# PWMSoldeerbout.net
KiCad netlist of a schematic drawn in Altium Designer
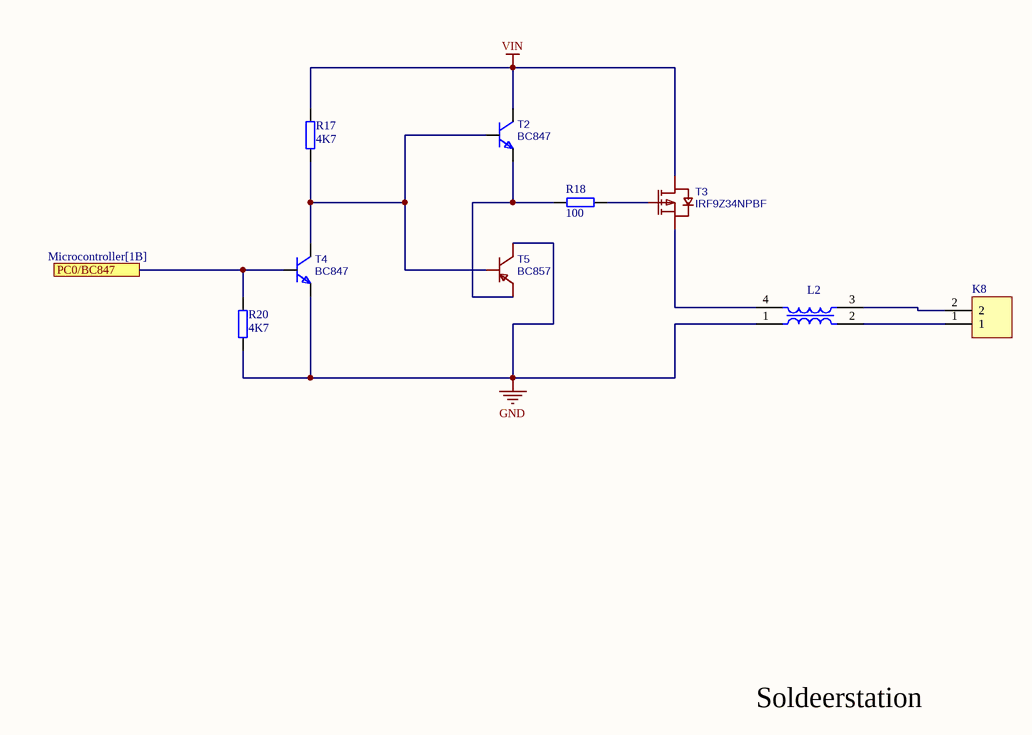
[diagram p0: PWMSoldeerbout.SchDoc]

(export (version "E")
  (design (tool "Eeschema 10.0.6"))
  (components
    (comp (ref "K8")
      (value "~")
      (footprint "Terminal_2")
      (libsource (lib "SoldeerStation") (part "K Terminal_2"))
    )
    (comp (ref "L2")
      (value "~")
      (footprint "L1 Smoorspoel")
      (description "Common Mode Chokes / Filters 170ohms 100MHz 10A 1 Choke SMD")
      (fields
        (field (name "MOUSER PART NUMBER") "875-CM2545X171R-10")
        (field (name "MANUFACTURER_PART_NUMBER") "CM2545X171R-10")
      )
      (libsource (lib "SoldeerStation") (part "L2 Common Mode Choke"))
    )
    (comp (ref "R17")
      (value "4K7")
      (footprint "RESC2013X50X30ML20T20")
      (fields (field (name "MANUFACTURER") "Vishay Dale") (field (name "PART NUMBER") "CRCW08050000Z0EA"))
      (libsource (lib "SoldeerStation") (part "R Resistor"))
    )
    (comp (ref "R18")
      (value "100")
      (footprint "RESC2013X50X30ML20T20")
      (fields (field (name "MANUFACTURER") "Vishay Dale") (field (name "PART NUMBER") "CRCW08050000Z0EA"))
      (libsource (lib "SoldeerStation") (part "R Resistor"))
    )
    (comp (ref "R20")
      (value "4K7")
      (footprint "RESC2013X50X30ML20T20")
      (fields (field (name "MANUFACTURER") "Vishay Dale") (field (name "PART NUMBER") "CRCW08050000Z0EA"))
      (libsource (lib "SoldeerStation") (part "R Resistor"))
    )
    (comp (ref "T2")
      (value "BC847")
      (footprint "T1,2,4 Bipolar Transistors")
      (description "BC847C_C3027113")
      (fields
        (field (name "BOM_SUPPLIER PART") "C3027113")
        (field (name "BOM_MANUFACTURER PART") "BC847C")
        (field (name "CONTRIBUTOR") "lcsc")
      )
      (libsource (lib "SoldeerStation") (part "T1,2,4 transisitors"))
    )
    (comp (ref "T3")
      (value "IRF9Z34NPBF")
      (footprint "T3 MOSFET-P")
      (fields (field (name "BOM_SUPPLIER PART") "C500523") (field (name "CONTRIBUTOR") "LCSC"))
      (libsource (lib "SoldeerStation") (part "T3 MOSFET-P"))
    )
    (comp (ref "T4")
      (value "BC847")
      (footprint "T1,2,4 Bipolar Transistors")
      (description "BC847C_C3027113")
      (fields
        (field (name "BOM_SUPPLIER PART") "C3027113")
        (field (name "BOM_MANUFACTURER PART") "BC847C")
        (field (name "CONTRIBUTOR") "lcsc")
      )
      (libsource (lib "SoldeerStation") (part "T1,2,4 transisitors"))
    )
    (comp (ref "T5")
      (value "BC857")
      (footprint "T5 Bipolar Transistors")
      (description "BC857 3G")
      (fields (field (name "BOM_SUPPLIER PART") "C2139"))
      (libsource (lib "SoldeerStation") (part "T5 Bipolar Transistor"))
    )
  )
  (nets
    (net (code "1") (name "/PC0{slash}BC847") (class "Default")
      (node (ref "R20") (pin "2") (pinfunction "2_2") (pintype "passive"))
      (node (ref "T4") (pin "1") (pinfunction "B_1") (pintype "passive"))
    )
    (net (code "2") (name "GND") (class "Default")
      (node (ref "L2") (pin "1") (pintype "passive"))
      (node (ref "R20") (pin "1") (pinfunction "1_1") (pintype "passive"))
      (node (ref "T4") (pin "2") (pinfunction "E_2") (pintype "passive"))
      (node (ref "T5") (pin "3") (pinfunction "3_3") (pintype "passive"))
    )
    (net (code "3") (name "Net-(K8-Pad1)") (class "Default")
      (node (ref "K8") (pin "1") (pinfunction "1_1") (pintype "passive"))
      (node (ref "L2") (pin "2") (pintype "passive"))
    )
    (net (code "4") (name "Net-(K8-Pad2)") (class "Default")
      (node (ref "K8") (pin "2") (pinfunction "2_2") (pintype "passive"))
      (node (ref "L2") (pin "3") (pintype "passive"))
    )
    (net (code "5") (name "Net-(T2-B)") (class "Default")
      (node (ref "R17") (pin "1") (pinfunction "1_1") (pintype "passive"))
      (node (ref "T2") (pin "1") (pinfunction "B_1") (pintype "passive"))
      (node (ref "T4") (pin "3") (pinfunction "C_3") (pintype "passive"))
      (node (ref "T5") (pin "1") (pinfunction "1_1") (pintype "passive"))
    )
    (net (code "6") (name "Net-(T2-E)") (class "Default")
      (node (ref "R18") (pin "2") (pinfunction "2_2") (pintype "passive"))
      (node (ref "T2") (pin "2") (pinfunction "E_2") (pintype "passive"))
      (node (ref "T5") (pin "2") (pinfunction "2_2") (pintype "passive"))
    )
    (net (code "7") (name "Net-(T3-G)") (class "Default")
      (node (ref "R18") (pin "1") (pinfunction "1_1") (pintype "passive"))
      (node (ref "T3") (pin "1") (pinfunction "G_1") (pintype "passive"))
    )
    (net (code "8") (name "Net-(T3-S)") (class "Default")
      (node (ref "L2") (pin "4") (pintype "passive"))
      (node (ref "T3") (pin "3") (pinfunction "S_3") (pintype "passive"))
    )
    (net (code "9") (name "VIN") (class "Default")
      (node (ref "R17") (pin "2") (pinfunction "2_2") (pintype "passive"))
      (node (ref "T2") (pin "3") (pinfunction "C_3") (pintype "passive"))
      (node (ref "T3") (pin "2") (pinfunction "D_2") (pintype "passive"))
    )
  )
)
